# xbeeDemoRecv.net
KiCad netlist of a schematic drawn in EAGLE
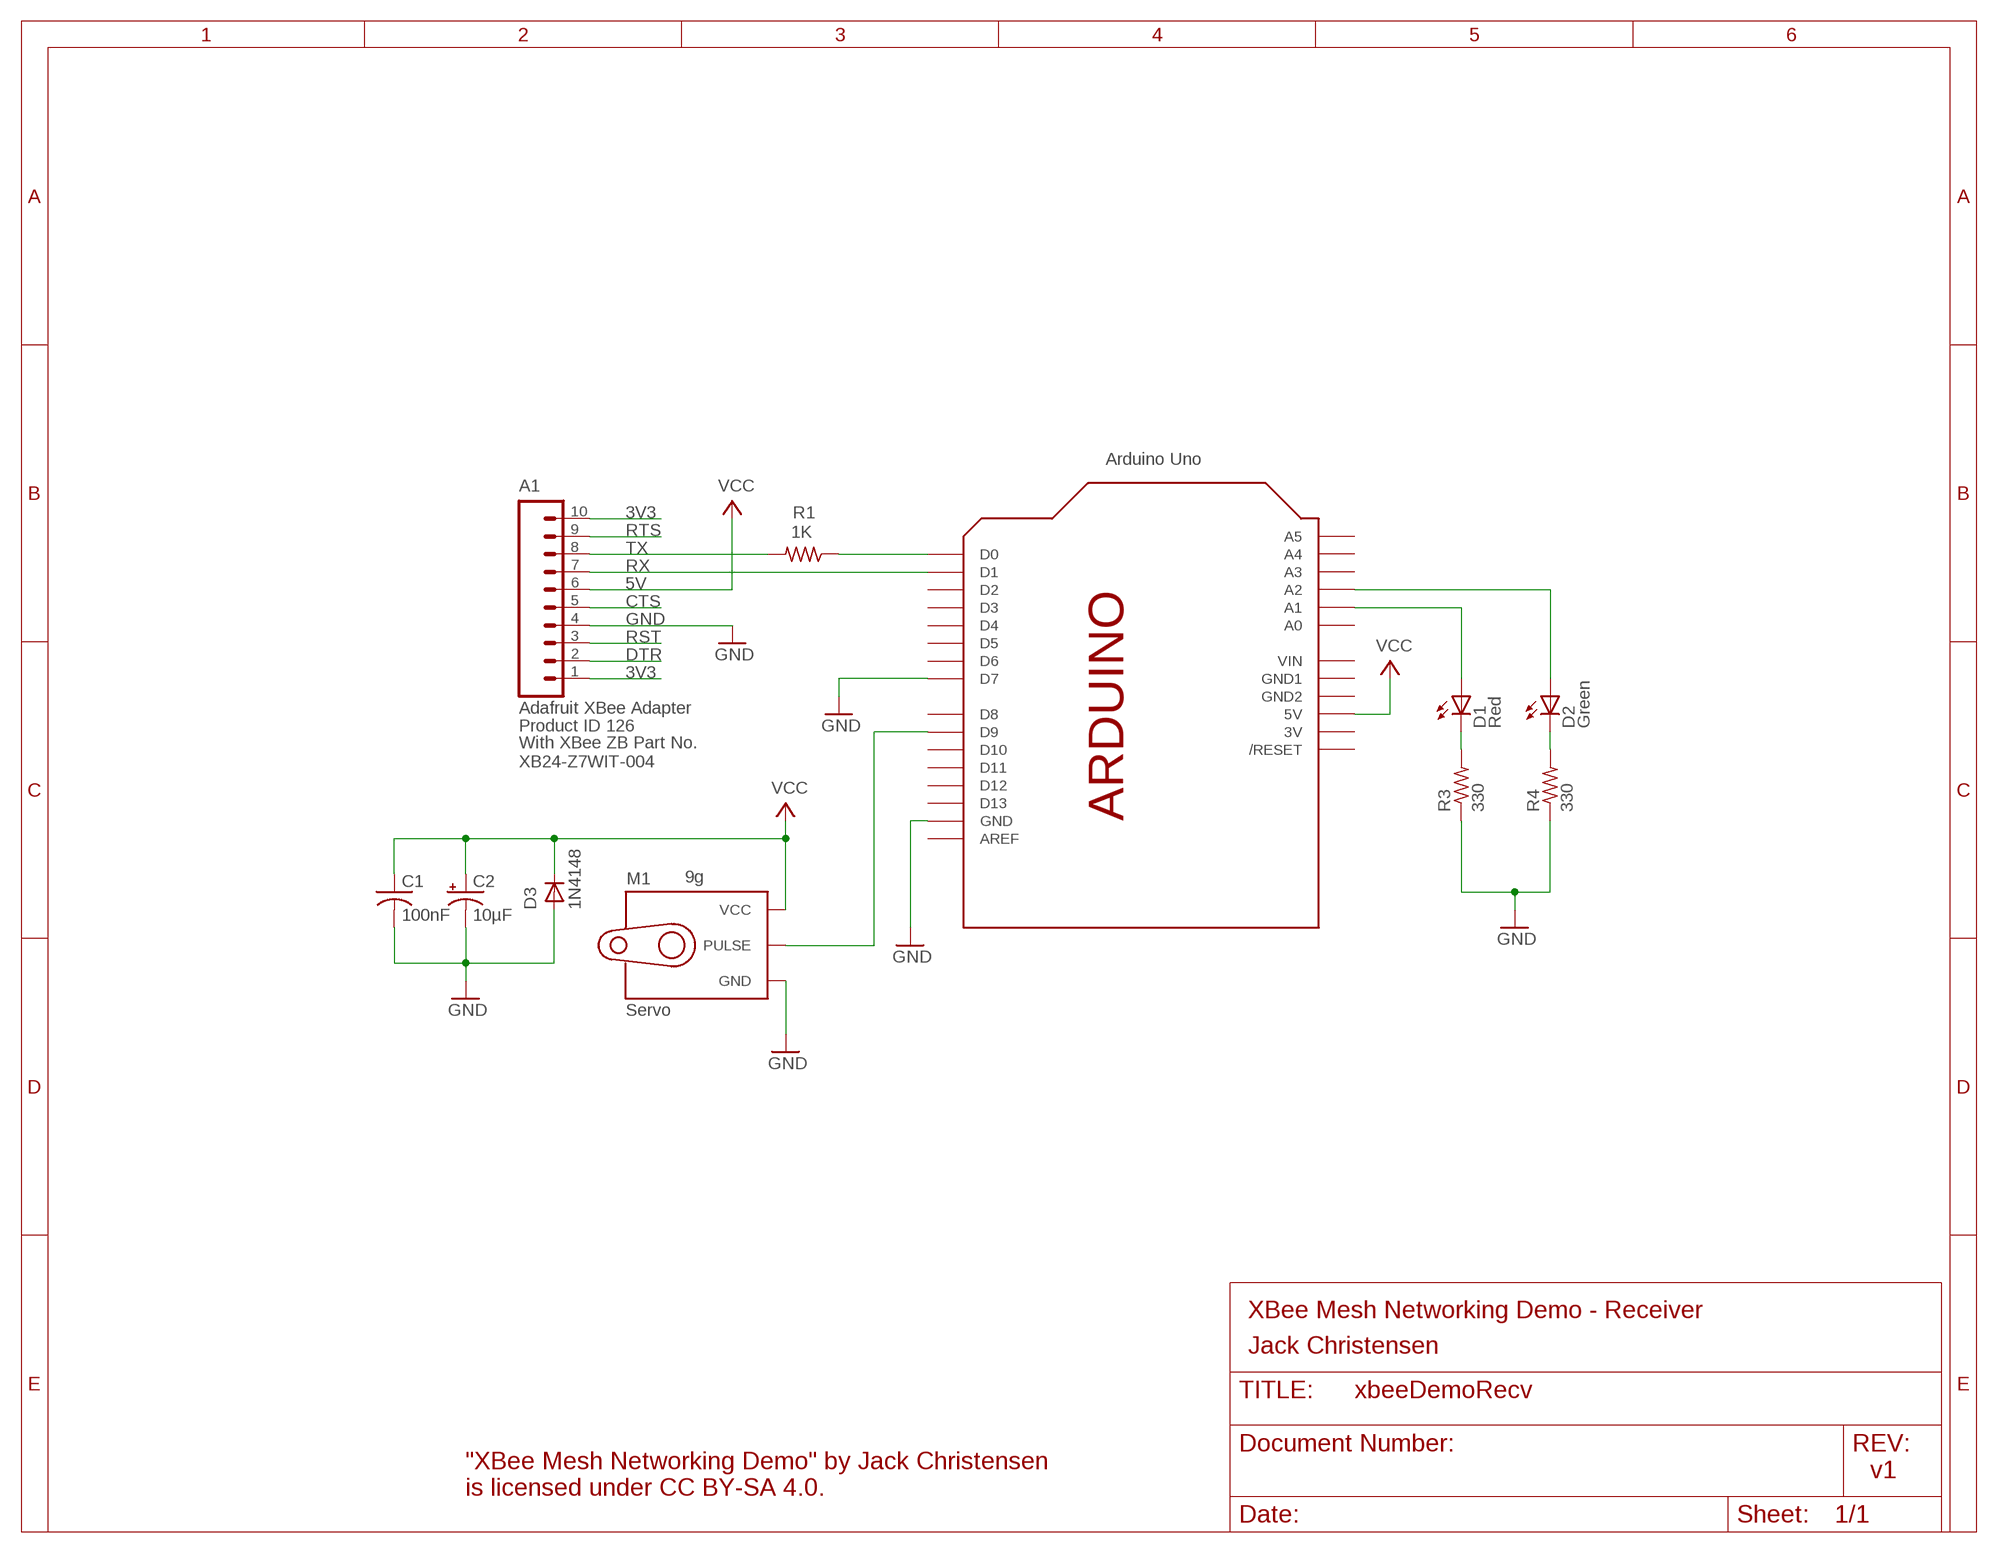
[diagram p0: schematic, sheet 1]

(export (version "E")
  (design (tool "Eeschema 10.0.6"))
  (components
    (comp (ref "A1")
      (value "Adafruit XBee Adapter")
      (footprint "eagle-import:1X10_LOCK")
      (libsource (lib "eagle-import") (part "M10LOCK"))
    )
    (comp (ref "C1")
      (value "100nF")
      (footprint "eagle-import:M0805")
      (libsource (lib "eagle-import") (part "C-USM0805"))
    )
    (comp (ref "C2")
      (value "10µF")
      (footprint "eagle-import:E5-4")
      (libsource (lib "eagle-import") (part "CPOL-USE5-4"))
    )
    (comp (ref "D1")
      (value "Red")
      (footprint "eagle-import:LED5MM")
      (libsource (lib "eagle-import") (part "LED5MM"))
    )
    (comp (ref "D2")
      (value "Green")
      (footprint "eagle-import:LED5MM")
      (libsource (lib "eagle-import") (part "LED5MM"))
    )
    (comp (ref "D3")
      (value "1N4148")
      (footprint "eagle-import:1N4148")
      (libsource (lib "eagle-import") (part "DIODE1N4148"))
    )
    (comp (ref "M1")
      (value "9g")
      (footprint "eagle-import:SERVO")
      (libsource (lib "eagle-import") (part "SERVO"))
    )
    (comp (ref "R1")
      (value "1K")
      (footprint "eagle-import:M0805")
      (libsource (lib "eagle-import") (part "R-US_M0805"))
    )
    (comp (ref "R3")
      (value "330")
      (footprint "eagle-import:M0805")
      (libsource (lib "eagle-import") (part "R-US_M0805"))
    )
    (comp (ref "R4")
      (value "330")
      (footprint "eagle-import:M0805")
      (libsource (lib "eagle-import") (part "R-US_M0805"))
    )
    (comp (ref "U$1")
      (value "ARDUINOUNO")
      (footprint "eagle-import:ARDUINO")
      (libsource (lib "eagle-import") (part "ARDUINOUNO"))
    )
  )
  (nets
    (net (code "1") (name "/3V") (class "Default")
      (node (ref "U$1") (pin "3V") (pinfunction "3V_3V") (pintype "power_in"))
    )
    (net (code "2") (name "/GND1") (class "Default")
      (node (ref "U$1") (pin "GND1") (pinfunction "GND1_GND1") (pintype "power_in"))
    )
    (net (code "3") (name "/GND2") (class "Default")
      (node (ref "U$1") (pin "GND2") (pinfunction "GND2_GND2") (pintype "power_in"))
    )
    (net (code "4") (name "/VIN") (class "Default")
      (node (ref "U$1") (pin "VIN") (pinfunction "VIN_VIN") (pintype "power_in"))
    )
    (net (code "5") (name "GND") (class "Default")
      (node (ref "A1") (pin "4") (pinfunction "4_4") (pintype "passive"))
      (node (ref "C1") (pin "2") (pinfunction "2_2") (pintype "passive"))
      (node (ref "C2") (pin "-") (pinfunction "-_-") (pintype "passive"))
      (node (ref "D3") (pin "A") (pinfunction "A_A") (pintype "passive"))
      (node (ref "M1") (pin "GND") (pinfunction "GND_GND") (pintype "bidirectional"))
      (node (ref "R3") (pin "1") (pinfunction "1_1") (pintype "passive"))
      (node (ref "R4") (pin "1") (pinfunction "1_1") (pintype "passive"))
      (node (ref "U$1") (pin "D7") (pinfunction "D7_D7") (pintype "bidirectional"))
      (node (ref "U$1") (pin "GND") (pinfunction "GND_GND") (pintype "power_in"))
    )
    (net (code "6") (name "Net-(A1-Pad7)") (class "Default")
      (node (ref "A1") (pin "7") (pinfunction "7_7") (pintype "passive"))
      (node (ref "U$1") (pin "D1") (pinfunction "D1_D1") (pintype "bidirectional"))
    )
    (net (code "7") (name "Net-(A1-Pad8)") (class "Default")
      (node (ref "A1") (pin "8") (pinfunction "8_8") (pintype "passive"))
      (node (ref "R1") (pin "2") (pinfunction "2_2") (pintype "passive"))
    )
    (net (code "8") (name "Net-(D1-C)") (class "Default")
      (node (ref "D1") (pin "K") (pinfunction "C_K") (pintype "passive"))
      (node (ref "R3") (pin "2") (pinfunction "2_2") (pintype "passive"))
    )
    (net (code "9") (name "Net-(D1-PadA)") (class "Default")
      (node (ref "D1") (pin "A") (pinfunction "A_A") (pintype "passive"))
      (node (ref "U$1") (pin "A1") (pinfunction "A1_A1") (pintype "bidirectional"))
    )
    (net (code "10") (name "Net-(D2-C)") (class "Default")
      (node (ref "D2") (pin "K") (pinfunction "C_K") (pintype "passive"))
      (node (ref "R4") (pin "2") (pinfunction "2_2") (pintype "passive"))
    )
    (net (code "11") (name "Net-(D2-PadA)") (class "Default")
      (node (ref "D2") (pin "A") (pinfunction "A_A") (pintype "passive"))
      (node (ref "U$1") (pin "A2") (pinfunction "A2_A2") (pintype "bidirectional"))
    )
    (net (code "12") (name "Net-(M1-PadPULSE)") (class "Default")
      (node (ref "M1") (pin "PULSE") (pinfunction "PULSE_PULSE") (pintype "bidirectional"))
      (node (ref "U$1") (pin "D9") (pinfunction "D9_D9") (pintype "bidirectional"))
    )
    (net (code "13") (name "Net-(R1-Pad1)") (class "Default")
      (node (ref "R1") (pin "1") (pinfunction "1_1") (pintype "passive"))
      (node (ref "U$1") (pin "D0") (pinfunction "D0_D0") (pintype "bidirectional"))
    )
    (net (code "14") (name "VCC") (class "Default")
      (node (ref "A1") (pin "6") (pinfunction "6_6") (pintype "passive"))
      (node (ref "C1") (pin "1") (pinfunction "1_1") (pintype "passive"))
      (node (ref "C2") (pin "+") (pinfunction "+_+") (pintype "passive"))
      (node (ref "D3") (pin "K") (pinfunction "K_K") (pintype "passive"))
      (node (ref "M1") (pin "VCC") (pinfunction "VCC_VCC") (pintype "bidirectional"))
      (node (ref "U$1") (pin "5V") (pinfunction "5V_5V") (pintype "power_in"))
    )
    (net (code "15") (name "unconnected-(A1-Pad1)") (class "Default")
      (node (ref "A1") (pin "1") (pinfunction "1_1") (pintype "passive"))
    )
    (net (code "16") (name "unconnected-(A1-Pad2)") (class "Default")
      (node (ref "A1") (pin "2") (pinfunction "2_2") (pintype "passive"))
    )
    (net (code "17") (name "unconnected-(A1-Pad3)") (class "Default")
      (node (ref "A1") (pin "3") (pinfunction "3_3") (pintype "passive"))
    )
    (net (code "18") (name "unconnected-(A1-Pad5)") (class "Default")
      (node (ref "A1") (pin "5") (pinfunction "5_5") (pintype "passive"))
    )
    (net (code "19") (name "unconnected-(A1-Pad9)") (class "Default")
      (node (ref "A1") (pin "9") (pinfunction "9_9") (pintype "passive"))
    )
    (net (code "20") (name "unconnected-(A1-Pad10)") (class "Default")
      (node (ref "A1") (pin "10") (pinfunction "10_10") (pintype "passive"))
    )
    (net (code "21") (name "unconnected-(U$1-PadA0)") (class "Default")
      (node (ref "U$1") (pin "A0") (pinfunction "A0_A0") (pintype "bidirectional"))
    )
    (net (code "22") (name "unconnected-(U$1-PadA3)") (class "Default")
      (node (ref "U$1") (pin "A3") (pinfunction "A3_A3") (pintype "bidirectional"))
    )
    (net (code "23") (name "unconnected-(U$1-PadA4)") (class "Default")
      (node (ref "U$1") (pin "A4") (pinfunction "A4_A4") (pintype "bidirectional"))
    )
    (net (code "24") (name "unconnected-(U$1-PadA5)") (class "Default")
      (node (ref "U$1") (pin "A5") (pinfunction "A5_A5") (pintype "bidirectional"))
    )
    (net (code "25") (name "unconnected-(U$1-PadAREF)") (class "Default")
      (node (ref "U$1") (pin "AREF") (pinfunction "AREF_AREF") (pintype "bidirectional"))
    )
    (net (code "26") (name "unconnected-(U$1-PadD2)") (class "Default")
      (node (ref "U$1") (pin "D2") (pinfunction "D2_D2") (pintype "bidirectional"))
    )
    (net (code "27") (name "unconnected-(U$1-PadD3)") (class "Default")
      (node (ref "U$1") (pin "D3") (pinfunction "D3_D3") (pintype "bidirectional"))
    )
    (net (code "28") (name "unconnected-(U$1-PadD4)") (class "Default")
      (node (ref "U$1") (pin "D4") (pinfunction "D4_D4") (pintype "bidirectional"))
    )
    (net (code "29") (name "unconnected-(U$1-PadD5)") (class "Default")
      (node (ref "U$1") (pin "D5") (pinfunction "D5_D5") (pintype "bidirectional"))
    )
    (net (code "30") (name "unconnected-(U$1-PadD6)") (class "Default")
      (node (ref "U$1") (pin "D6") (pinfunction "D6_D6") (pintype "bidirectional"))
    )
    (net (code "31") (name "unconnected-(U$1-PadD8)") (class "Default")
      (node (ref "U$1") (pin "D8") (pinfunction "D8_D8") (pintype "bidirectional"))
    )
    (net (code "32") (name "unconnected-(U$1-PadD10)") (class "Default")
      (node (ref "U$1") (pin "D10") (pinfunction "D10_D10") (pintype "bidirectional"))
    )
    (net (code "33") (name "unconnected-(U$1-PadD11)") (class "Default")
      (node (ref "U$1") (pin "D11") (pinfunction "D11_D11") (pintype "bidirectional"))
    )
    (net (code "34") (name "unconnected-(U$1-PadD12)") (class "Default")
      (node (ref "U$1") (pin "D12") (pinfunction "D12_D12") (pintype "bidirectional"))
    )
    (net (code "35") (name "unconnected-(U$1-PadD13)") (class "Default")
      (node (ref "U$1") (pin "D13") (pinfunction "D13_D13") (pintype "bidirectional"))
    )
    (net (code "36") (name "unconnected-(U$1-{slash}RESET-PadRESET)") (class "Default")
      (node (ref "U$1") (pin "RESET") (pinfunction "/RESET_RESET") (pintype "bidirectional"))
    )
  )
)
